# EPS_MPPT_XY_Measurements.net
KiCad netlist of a schematic drawn in Altium Designer
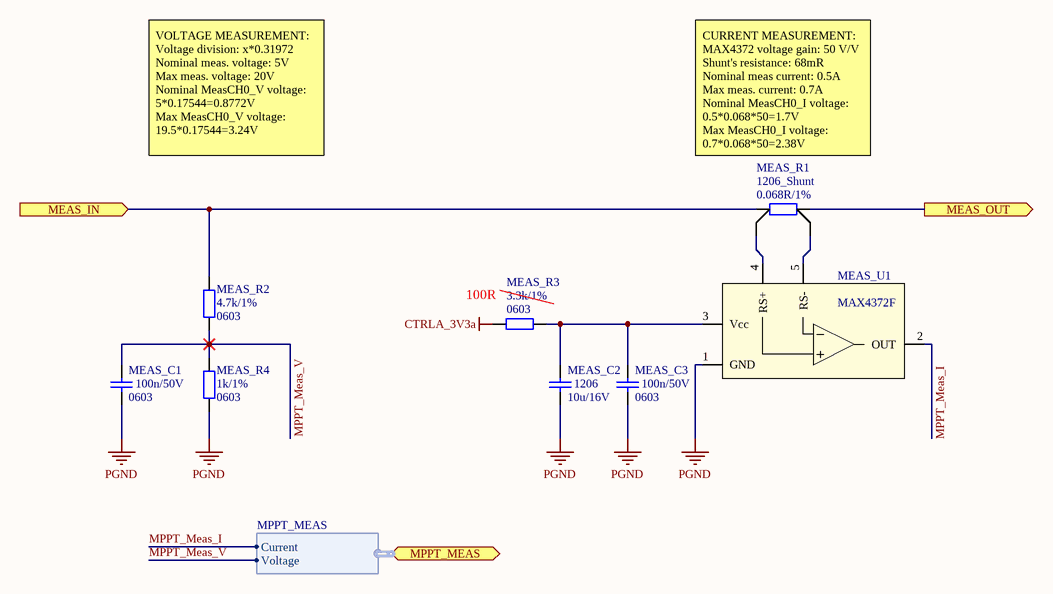
[diagram p0: EPS_MPPT_XY_Measurements.SchDoc]

(export (version "E")
  (design (tool "Eeschema 10.0.6"))
  (components
    (comp (ref "MEAS_C1")
      (value "100n/50V")
      (footprint "SMD_Capacitor_0603")
      (description "Ceramic Cap Kemet COTS 100n/50V X7R 0603")
      (fields
        (field (name "MANUFACTURER") "Kemet")
        (field (name "MANUFACTURERPARTNUMBER") "C0603T104K5RALTU")
        (field (name "PACKAGE") "0603")
      )
      (libsource (lib "capacitors") (part "Cer_C0603T104K5RALTU"))
    )
    (comp (ref "MEAS_C2")
      (value "10u/16V")
      (footprint "SMD_Capacitor_1206")
      (description "Ceramic Cap Kemet COTS 10u/16V X7R 1206")
      (fields
        (field (name "MANUFACTURERPARTNUMBER") "C1206T106K4RACTU")
        (field (name "MANUFACTURER") "Kemet")
        (field (name "PACKGE") "1206")
      )
      (libsource (lib "capacitors") (part "Cer_C1206T106K4RACTU"))
    )
    (comp (ref "MEAS_C3")
      (value "100n/50V")
      (footprint "SMD_Capacitor_0603")
      (description "Ceramic Cap Kemet COTS 100n/50V X7R 0603")
      (fields
        (field (name "MANUFACTURER") "Kemet")
        (field (name "MANUFACTURERPARTNUMBER") "C0603T104K5RALTU")
        (field (name "PACKAGE") "0603")
      )
      (libsource (lib "capacitors") (part "Cer_C0603T104K5RALTU"))
    )
    (comp (ref "MEAS_R1")
      (value "0.068R/1%")
      (footprint "SMD_Resistor-Shunt_1206")
      (description "Panasonic Resistor 68mR 1% 1206 1W")
      (fields
        (field (name "MANUFACTURER") "Panasonic")
        (field (name "MANUFACTURERPARTNUMBER") "ERJ-8BWFR068V")
        (field (name "PACKAGE") "1206_Shunt")
      )
      (libsource (lib "resistors") (part "ERJ-8BWFR068V"))
    )
    (comp (ref "MEAS_R2")
      (value "4.7k/1%")
      (footprint "SMD_Resistor_0603")
      (fields (field (name "PACKAGE") "0603"))
      (libsource (lib "resistors") (part "Res"))
    )
    (comp (ref "MEAS_R3")
      (value "3.3k/1%")
      (footprint "SMD_Resistor_0603")
      (fields (field (name "PACKAGE") "0603"))
      (libsource (lib "") (part "Res_1"))
    )
    (comp (ref "MEAS_R4")
      (value "1k/1%")
      (footprint "SMD_Resistor_0603")
      (fields (field (name "PACKAGE") "0603"))
      (libsource (lib "resistors") (part "Res"))
    )
    (comp (ref "MEAS_U1")
      (value "MAX4372F")
      (footprint "SOT23-5")
      (description "High-Side Current-Sense Amplifier with Voltage Output")
      (fields (field (name "MANUFACTURER") "Maxim Integrated Products"))
      (libsource (lib "microcircuits") (part "MAX4372"))
    )
  )
  (nets
    (net (code "2") (name "/MEAS_IN") (class "Default")
      (node (ref "MEAS_R1") (pin "1") (pinfunction "1_1") (pintype "passive"))
      (node (ref "MEAS_R2") (pin "1") (pinfunction "1_1") (pintype "passive"))
    )
    (net (code "3") (name "/MEAS_OUT") (class "Default")
      (node (ref "MEAS_R1") (pin "4") (pinfunction "4_4") (pintype "passive"))
    )
    (net (code "4") (name "/MPPT_Meas_I") (class "Default")
      (node (ref "MEAS_U1") (pin "2") (pinfunction "OUT_2") (pintype "passive"))
    )
    (net (code "5") (name "/MPPT_Meas_V") (class "Default")
      (node (ref "MEAS_C1") (pin "1") (pinfunction "1_1") (pintype "passive"))
      (node (ref "MEAS_R2") (pin "2") (pinfunction "2_2") (pintype "passive"))
      (node (ref "MEAS_R4") (pin "1") (pinfunction "1_1") (pintype "passive"))
    )
    (net (code "7") (name "CTRLA_3V3a") (class "Default")
      (node (ref "MEAS_R3") (pin "1") (pinfunction "1_1") (pintype "passive"))
    )
    (net (code "8") (name "Net-(MEAS_U1-RS+)") (class "Default")
      (node (ref "MEAS_R1") (pin "2") (pinfunction "2_2") (pintype "passive"))
      (node (ref "MEAS_U1") (pin "4") (pinfunction "RS+_4") (pintype "passive"))
    )
    (net (code "9") (name "Net-(MEAS_U1-RS-)") (class "Default")
      (node (ref "MEAS_R1") (pin "3") (pinfunction "3_3") (pintype "passive"))
      (node (ref "MEAS_U1") (pin "5") (pinfunction "RS-_5") (pintype "passive"))
    )
    (net (code "10") (name "Net-(MEAS_U1-Vcc)") (class "Default")
      (node (ref "MEAS_C2") (pin "1") (pinfunction "1_1") (pintype "passive"))
      (node (ref "MEAS_C3") (pin "1") (pinfunction "1_1") (pintype "passive"))
      (node (ref "MEAS_R3") (pin "2") (pinfunction "2_2") (pintype "passive"))
      (node (ref "MEAS_U1") (pin "3") (pinfunction "Vcc_3") (pintype "passive"))
    )
    (net (code "11") (name "PGND") (class "Default")
      (node (ref "MEAS_C1") (pin "2") (pinfunction "2_2") (pintype "passive"))
      (node (ref "MEAS_C2") (pin "2") (pinfunction "2_2") (pintype "passive"))
      (node (ref "MEAS_C3") (pin "2") (pinfunction "2_2") (pintype "passive"))
      (node (ref "MEAS_R4") (pin "2") (pinfunction "2_2") (pintype "passive"))
      (node (ref "MEAS_U1") (pin "1") (pinfunction "GND_1") (pintype "passive"))
    )
  )
)
